# light_cube.net
KiCad netlist of a schematic drawn in EAGLE
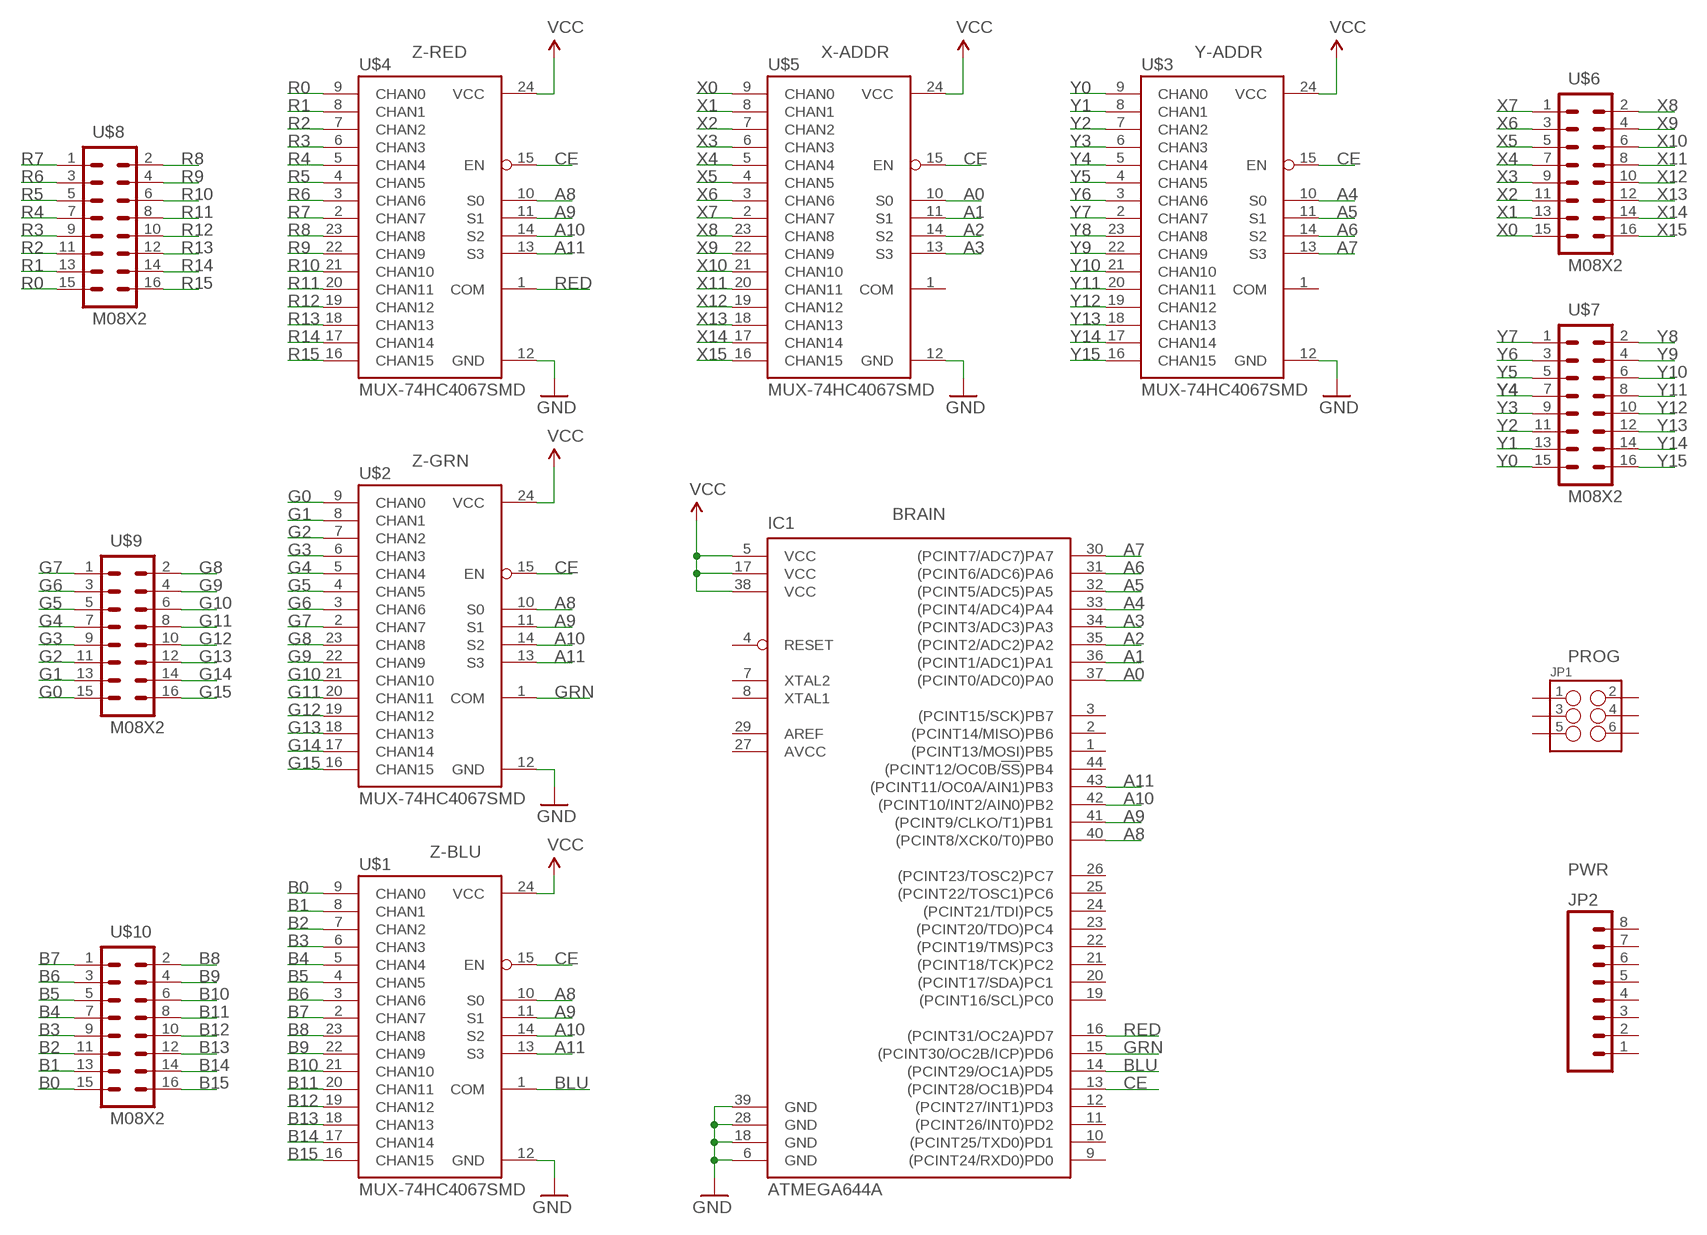
[diagram p0: schematic, sheet 1]

(export (version "E")
  (design (tool "Eeschema 10.0.6"))
  (components
    (comp (ref "IC1")
      (value "ATMEGA644A")
      (footprint "eagle-import:TQFP44")
      (fields (field (name "MPN") "ATMEGA644PV-10AU"))
      (libsource (lib "eagle-import") (part "ATMEGA644A"))
    )
    (comp (ref "JP1")
      (value "M03X2NO_SILK")
      (footprint "eagle-import:2X3-NS")
      (libsource (lib "eagle-import") (part "M03X2NO_SILK"))
    )
    (comp (ref "JP2")
      (value "M081X08")
      (footprint "eagle-import:1X08")
      (libsource (lib "eagle-import") (part "M081X08"))
    )
    (comp (ref "U$1")
      (value "MUX-74HC4067SMD")
      (footprint "eagle-import:SSOP24")
      (libsource (lib "eagle-import") (part "MUX-74HC4067SMD"))
    )
    (comp (ref "U$2")
      (value "MUX-74HC4067SMD")
      (footprint "eagle-import:SSOP24")
      (libsource (lib "eagle-import") (part "MUX-74HC4067SMD"))
    )
    (comp (ref "U$3")
      (value "MUX-74HC4067SMD")
      (footprint "eagle-import:SSOP24")
      (libsource (lib "eagle-import") (part "MUX-74HC4067SMD"))
    )
    (comp (ref "U$4")
      (value "MUX-74HC4067SMD")
      (footprint "eagle-import:SSOP24")
      (libsource (lib "eagle-import") (part "MUX-74HC4067SMD"))
    )
    (comp (ref "U$5")
      (value "MUX-74HC4067SMD")
      (footprint "eagle-import:SSOP24")
      (libsource (lib "eagle-import") (part "MUX-74HC4067SMD"))
    )
    (comp (ref "U$6")
      (value "M08X2")
      (footprint "eagle-import:2X8")
      (libsource (lib "eagle-import") (part "M08X2"))
    )
    (comp (ref "U$7")
      (value "M08X2")
      (footprint "eagle-import:2X8")
      (libsource (lib "eagle-import") (part "M08X2"))
    )
    (comp (ref "U$8")
      (value "M08X2")
      (footprint "eagle-import:2X8")
      (libsource (lib "eagle-import") (part "M08X2"))
    )
    (comp (ref "U$9")
      (value "M08X2")
      (footprint "eagle-import:2X8")
      (libsource (lib "eagle-import") (part "M08X2"))
    )
    (comp (ref "U$10")
      (value "M08X2")
      (footprint "eagle-import:2X8")
      (libsource (lib "eagle-import") (part "M08X2"))
    )
  )
  (nets
    (net (code "1") (name "/A0") (class "Default")
      (node (ref "IC1") (pin "37") (pinfunction "(PCINT0/ADC0)PA0_37") (pintype "bidirectional"))
      (node (ref "U$5") (pin "10") (pinfunction "S0_10") (pintype "input"))
    )
    (net (code "2") (name "/A1") (class "Default")
      (node (ref "IC1") (pin "36") (pinfunction "(PCINT1/ADC1)PA1_36") (pintype "bidirectional"))
      (node (ref "U$5") (pin "11") (pinfunction "S1_11") (pintype "input"))
    )
    (net (code "3") (name "/A2") (class "Default")
      (node (ref "IC1") (pin "35") (pinfunction "(PCINT2/ADC2)PA2_35") (pintype "bidirectional"))
      (node (ref "U$5") (pin "14") (pinfunction "S2_14") (pintype "input"))
    )
    (net (code "4") (name "/A3") (class "Default")
      (node (ref "IC1") (pin "34") (pinfunction "(PCINT3/ADC3)PA3_34") (pintype "bidirectional"))
      (node (ref "U$5") (pin "13") (pinfunction "S3_13") (pintype "input"))
    )
    (net (code "5") (name "/A4") (class "Default")
      (node (ref "IC1") (pin "33") (pinfunction "(PCINT4/ADC4)PA4_33") (pintype "bidirectional"))
      (node (ref "U$3") (pin "10") (pinfunction "S0_10") (pintype "input"))
    )
    (net (code "6") (name "/A5") (class "Default")
      (node (ref "IC1") (pin "32") (pinfunction "(PCINT5/ADC5)PA5_32") (pintype "bidirectional"))
      (node (ref "U$3") (pin "11") (pinfunction "S1_11") (pintype "input"))
    )
    (net (code "7") (name "/A6") (class "Default")
      (node (ref "IC1") (pin "31") (pinfunction "(PCINT6/ADC6)PA6_31") (pintype "bidirectional"))
      (node (ref "U$3") (pin "14") (pinfunction "S2_14") (pintype "input"))
    )
    (net (code "8") (name "/A7") (class "Default")
      (node (ref "IC1") (pin "30") (pinfunction "(PCINT7/ADC7)PA7_30") (pintype "bidirectional"))
      (node (ref "U$3") (pin "13") (pinfunction "S3_13") (pintype "input"))
    )
    (net (code "9") (name "/A8") (class "Default")
      (node (ref "IC1") (pin "40") (pinfunction "(PCINT8/XCK0/T0)PB0_40") (pintype "bidirectional"))
      (node (ref "U$1") (pin "10") (pinfunction "S0_10") (pintype "input"))
      (node (ref "U$2") (pin "10") (pinfunction "S0_10") (pintype "input"))
      (node (ref "U$4") (pin "10") (pinfunction "S0_10") (pintype "input"))
    )
    (net (code "10") (name "/A9") (class "Default")
      (node (ref "IC1") (pin "41") (pinfunction "(PCINT9/CLKO/T1)PB1_41") (pintype "bidirectional"))
      (node (ref "U$1") (pin "11") (pinfunction "S1_11") (pintype "input"))
      (node (ref "U$2") (pin "11") (pinfunction "S1_11") (pintype "input"))
      (node (ref "U$4") (pin "11") (pinfunction "S1_11") (pintype "input"))
    )
    (net (code "11") (name "/A10") (class "Default")
      (node (ref "IC1") (pin "42") (pinfunction "(PCINT10/INT2/AIN0)PB2_42") (pintype "bidirectional"))
      (node (ref "U$1") (pin "14") (pinfunction "S2_14") (pintype "input"))
      (node (ref "U$2") (pin "14") (pinfunction "S2_14") (pintype "input"))
      (node (ref "U$4") (pin "14") (pinfunction "S2_14") (pintype "input"))
    )
    (net (code "12") (name "/A11") (class "Default")
      (node (ref "IC1") (pin "43") (pinfunction "(PCINT11/OC0A/AIN1)PB3_43") (pintype "bidirectional"))
      (node (ref "U$1") (pin "13") (pinfunction "S3_13") (pintype "input"))
      (node (ref "U$2") (pin "13") (pinfunction "S3_13") (pintype "input"))
      (node (ref "U$4") (pin "13") (pinfunction "S3_13") (pintype "input"))
    )
    (net (code "13") (name "/AVCC") (class "Default")
      (node (ref "IC1") (pin "27") (pinfunction "AVCC_27") (pintype "power_in"))
    )
    (net (code "14") (name "/B0") (class "Default")
      (node (ref "U$1") (pin "9") (pinfunction "CHAN0_9") (pintype "bidirectional"))
      (node (ref "U$10") (pin "15") (pinfunction "15_15") (pintype "passive"))
    )
    (net (code "15") (name "/B1") (class "Default")
      (node (ref "U$1") (pin "8") (pinfunction "CHAN1_8") (pintype "bidirectional"))
      (node (ref "U$10") (pin "13") (pinfunction "13_13") (pintype "passive"))
    )
    (net (code "16") (name "/B2") (class "Default")
      (node (ref "U$1") (pin "7") (pinfunction "CHAN2_7") (pintype "bidirectional"))
      (node (ref "U$10") (pin "11") (pinfunction "11_11") (pintype "passive"))
    )
    (net (code "17") (name "/B3") (class "Default")
      (node (ref "U$1") (pin "6") (pinfunction "CHAN3_6") (pintype "bidirectional"))
      (node (ref "U$10") (pin "9") (pinfunction "9_9") (pintype "passive"))
    )
    (net (code "18") (name "/B4") (class "Default")
      (node (ref "U$1") (pin "5") (pinfunction "CHAN4_5") (pintype "bidirectional"))
      (node (ref "U$10") (pin "7") (pinfunction "7_7") (pintype "passive"))
    )
    (net (code "19") (name "/B5") (class "Default")
      (node (ref "U$1") (pin "4") (pinfunction "CHAN5_4") (pintype "bidirectional"))
      (node (ref "U$10") (pin "5") (pinfunction "5_5") (pintype "passive"))
    )
    (net (code "20") (name "/B6") (class "Default")
      (node (ref "U$1") (pin "3") (pinfunction "CHAN6_3") (pintype "bidirectional"))
      (node (ref "U$10") (pin "3") (pinfunction "3_3") (pintype "passive"))
    )
    (net (code "21") (name "/B7") (class "Default")
      (node (ref "U$1") (pin "2") (pinfunction "CHAN7_2") (pintype "bidirectional"))
      (node (ref "U$10") (pin "1") (pinfunction "1_1") (pintype "passive"))
    )
    (net (code "22") (name "/B8") (class "Default")
      (node (ref "U$1") (pin "23") (pinfunction "CHAN8_23") (pintype "bidirectional"))
      (node (ref "U$10") (pin "2") (pinfunction "2_2") (pintype "passive"))
    )
    (net (code "23") (name "/B9") (class "Default")
      (node (ref "U$1") (pin "22") (pinfunction "CHAN9_22") (pintype "bidirectional"))
      (node (ref "U$10") (pin "4") (pinfunction "4_4") (pintype "passive"))
    )
    (net (code "24") (name "/B10") (class "Default")
      (node (ref "U$1") (pin "21") (pinfunction "CHAN10_21") (pintype "bidirectional"))
      (node (ref "U$10") (pin "6") (pinfunction "6_6") (pintype "passive"))
    )
    (net (code "25") (name "/B11") (class "Default")
      (node (ref "U$1") (pin "20") (pinfunction "CHAN11_20") (pintype "bidirectional"))
      (node (ref "U$10") (pin "8") (pinfunction "8_8") (pintype "passive"))
    )
    (net (code "26") (name "/B12") (class "Default")
      (node (ref "U$1") (pin "19") (pinfunction "CHAN12_19") (pintype "bidirectional"))
      (node (ref "U$10") (pin "10") (pinfunction "10_10") (pintype "passive"))
    )
    (net (code "27") (name "/B13") (class "Default")
      (node (ref "U$1") (pin "18") (pinfunction "CHAN13_18") (pintype "bidirectional"))
      (node (ref "U$10") (pin "12") (pinfunction "12_12") (pintype "passive"))
    )
    (net (code "28") (name "/B14") (class "Default")
      (node (ref "U$1") (pin "17") (pinfunction "CHAN14_17") (pintype "bidirectional"))
      (node (ref "U$10") (pin "14") (pinfunction "14_14") (pintype "passive"))
    )
    (net (code "29") (name "/B15") (class "Default")
      (node (ref "U$1") (pin "16") (pinfunction "CHAN15_16") (pintype "bidirectional"))
      (node (ref "U$10") (pin "16") (pinfunction "16_16") (pintype "passive"))
    )
    (net (code "30") (name "/BLU") (class "Default")
      (node (ref "IC1") (pin "14") (pinfunction "(PCINT29/OC1A)PD5_14") (pintype "bidirectional"))
      (node (ref "U$1") (pin "1") (pinfunction "COM_1") (pintype "bidirectional"))
    )
    (net (code "31") (name "/CE") (class "Default")
      (node (ref "IC1") (pin "13") (pinfunction "(PCINT28/OC1B)PD4_13") (pintype "bidirectional"))
      (node (ref "U$1") (pin "15") (pinfunction "EN_15") (pintype "input"))
      (node (ref "U$2") (pin "15") (pinfunction "EN_15") (pintype "input"))
      (node (ref "U$3") (pin "15") (pinfunction "EN_15") (pintype "input"))
      (node (ref "U$4") (pin "15") (pinfunction "EN_15") (pintype "input"))
      (node (ref "U$5") (pin "15") (pinfunction "EN_15") (pintype "input"))
    )
    (net (code "32") (name "/G0") (class "Default")
      (node (ref "U$2") (pin "9") (pinfunction "CHAN0_9") (pintype "bidirectional"))
      (node (ref "U$9") (pin "15") (pinfunction "15_15") (pintype "passive"))
    )
    (net (code "33") (name "/G1") (class "Default")
      (node (ref "U$2") (pin "8") (pinfunction "CHAN1_8") (pintype "bidirectional"))
      (node (ref "U$9") (pin "13") (pinfunction "13_13") (pintype "passive"))
    )
    (net (code "34") (name "/G2") (class "Default")
      (node (ref "U$2") (pin "7") (pinfunction "CHAN2_7") (pintype "bidirectional"))
      (node (ref "U$9") (pin "11") (pinfunction "11_11") (pintype "passive"))
    )
    (net (code "35") (name "/G3") (class "Default")
      (node (ref "U$2") (pin "6") (pinfunction "CHAN3_6") (pintype "bidirectional"))
      (node (ref "U$9") (pin "9") (pinfunction "9_9") (pintype "passive"))
    )
    (net (code "36") (name "/G4") (class "Default")
      (node (ref "U$2") (pin "5") (pinfunction "CHAN4_5") (pintype "bidirectional"))
      (node (ref "U$9") (pin "7") (pinfunction "7_7") (pintype "passive"))
    )
    (net (code "37") (name "/G5") (class "Default")
      (node (ref "U$2") (pin "4") (pinfunction "CHAN5_4") (pintype "bidirectional"))
      (node (ref "U$9") (pin "5") (pinfunction "5_5") (pintype "passive"))
    )
    (net (code "38") (name "/G6") (class "Default")
      (node (ref "U$2") (pin "3") (pinfunction "CHAN6_3") (pintype "bidirectional"))
      (node (ref "U$9") (pin "3") (pinfunction "3_3") (pintype "passive"))
    )
    (net (code "39") (name "/G7") (class "Default")
      (node (ref "U$2") (pin "2") (pinfunction "CHAN7_2") (pintype "bidirectional"))
      (node (ref "U$9") (pin "1") (pinfunction "1_1") (pintype "passive"))
    )
    (net (code "40") (name "/G8") (class "Default")
      (node (ref "U$2") (pin "23") (pinfunction "CHAN8_23") (pintype "bidirectional"))
      (node (ref "U$9") (pin "2") (pinfunction "2_2") (pintype "passive"))
    )
    (net (code "41") (name "/G9") (class "Default")
      (node (ref "U$2") (pin "22") (pinfunction "CHAN9_22") (pintype "bidirectional"))
      (node (ref "U$9") (pin "4") (pinfunction "4_4") (pintype "passive"))
    )
    (net (code "42") (name "/G10") (class "Default")
      (node (ref "U$2") (pin "21") (pinfunction "CHAN10_21") (pintype "bidirectional"))
      (node (ref "U$9") (pin "6") (pinfunction "6_6") (pintype "passive"))
    )
    (net (code "43") (name "/G11") (class "Default")
      (node (ref "U$2") (pin "20") (pinfunction "CHAN11_20") (pintype "bidirectional"))
      (node (ref "U$9") (pin "8") (pinfunction "8_8") (pintype "passive"))
    )
    (net (code "44") (name "/G12") (class "Default")
      (node (ref "U$2") (pin "19") (pinfunction "CHAN12_19") (pintype "bidirectional"))
      (node (ref "U$9") (pin "10") (pinfunction "10_10") (pintype "passive"))
    )
    (net (code "45") (name "/G13") (class "Default")
      (node (ref "U$2") (pin "18") (pinfunction "CHAN13_18") (pintype "bidirectional"))
      (node (ref "U$9") (pin "12") (pinfunction "12_12") (pintype "passive"))
    )
    (net (code "46") (name "/G14") (class "Default")
      (node (ref "U$2") (pin "17") (pinfunction "CHAN14_17") (pintype "bidirectional"))
      (node (ref "U$9") (pin "14") (pinfunction "14_14") (pintype "passive"))
    )
    (net (code "47") (name "/G15") (class "Default")
      (node (ref "U$2") (pin "16") (pinfunction "CHAN15_16") (pintype "bidirectional"))
      (node (ref "U$9") (pin "16") (pinfunction "16_16") (pintype "passive"))
    )
    (net (code "48") (name "/GRN") (class "Default")
      (node (ref "IC1") (pin "15") (pinfunction "(PCINT30/OC2B/ICP)PD6_15") (pintype "bidirectional"))
      (node (ref "U$2") (pin "1") (pinfunction "COM_1") (pintype "bidirectional"))
    )
    (net (code "49") (name "/R0") (class "Default")
      (node (ref "U$4") (pin "9") (pinfunction "CHAN0_9") (pintype "bidirectional"))
      (node (ref "U$8") (pin "15") (pinfunction "15_15") (pintype "passive"))
    )
    (net (code "50") (name "/R1") (class "Default")
      (node (ref "U$4") (pin "8") (pinfunction "CHAN1_8") (pintype "bidirectional"))
      (node (ref "U$8") (pin "13") (pinfunction "13_13") (pintype "passive"))
    )
    (net (code "51") (name "/R2") (class "Default")
      (node (ref "U$4") (pin "7") (pinfunction "CHAN2_7") (pintype "bidirectional"))
      (node (ref "U$8") (pin "11") (pinfunction "11_11") (pintype "passive"))
    )
    (net (code "52") (name "/R3") (class "Default")
      (node (ref "U$4") (pin "6") (pinfunction "CHAN3_6") (pintype "bidirectional"))
      (node (ref "U$8") (pin "9") (pinfunction "9_9") (pintype "passive"))
    )
    (net (code "53") (name "/R4") (class "Default")
      (node (ref "U$4") (pin "5") (pinfunction "CHAN4_5") (pintype "bidirectional"))
      (node (ref "U$8") (pin "7") (pinfunction "7_7") (pintype "passive"))
    )
    (net (code "54") (name "/R5") (class "Default")
      (node (ref "U$4") (pin "4") (pinfunction "CHAN5_4") (pintype "bidirectional"))
      (node (ref "U$8") (pin "5") (pinfunction "5_5") (pintype "passive"))
    )
    (net (code "55") (name "/R6") (class "Default")
      (node (ref "U$4") (pin "3") (pinfunction "CHAN6_3") (pintype "bidirectional"))
      (node (ref "U$8") (pin "3") (pinfunction "3_3") (pintype "passive"))
    )
    (net (code "56") (name "/R7") (class "Default")
      (node (ref "U$4") (pin "2") (pinfunction "CHAN7_2") (pintype "bidirectional"))
      (node (ref "U$8") (pin "1") (pinfunction "1_1") (pintype "passive"))
    )
    (net (code "57") (name "/R8") (class "Default")
      (node (ref "U$4") (pin "23") (pinfunction "CHAN8_23") (pintype "bidirectional"))
      (node (ref "U$8") (pin "2") (pinfunction "2_2") (pintype "passive"))
    )
    (net (code "58") (name "/R9") (class "Default")
      (node (ref "U$4") (pin "22") (pinfunction "CHAN9_22") (pintype "bidirectional"))
      (node (ref "U$8") (pin "4") (pinfunction "4_4") (pintype "passive"))
    )
    (net (code "59") (name "/R10") (class "Default")
      (node (ref "U$4") (pin "21") (pinfunction "CHAN10_21") (pintype "bidirectional"))
      (node (ref "U$8") (pin "6") (pinfunction "6_6") (pintype "passive"))
    )
    (net (code "60") (name "/R11") (class "Default")
      (node (ref "U$4") (pin "20") (pinfunction "CHAN11_20") (pintype "bidirectional"))
      (node (ref "U$8") (pin "8") (pinfunction "8_8") (pintype "passive"))
    )
    (net (code "61") (name "/R12") (class "Default")
      (node (ref "U$4") (pin "19") (pinfunction "CHAN12_19") (pintype "bidirectional"))
      (node (ref "U$8") (pin "10") (pinfunction "10_10") (pintype "passive"))
    )
    (net (code "62") (name "/R13") (class "Default")
      (node (ref "U$4") (pin "18") (pinfunction "CHAN13_18") (pintype "bidirectional"))
      (node (ref "U$8") (pin "12") (pinfunction "12_12") (pintype "passive"))
    )
    (net (code "63") (name "/R14") (class "Default")
      (node (ref "U$4") (pin "17") (pinfunction "CHAN14_17") (pintype "bidirectional"))
      (node (ref "U$8") (pin "14") (pinfunction "14_14") (pintype "passive"))
    )
    (net (code "64") (name "/R15") (class "Default")
      (node (ref "U$4") (pin "16") (pinfunction "CHAN15_16") (pintype "bidirectional"))
      (node (ref "U$8") (pin "16") (pinfunction "16_16") (pintype "passive"))
    )
    (net (code "65") (name "/RED") (class "Default")
      (node (ref "IC1") (pin "16") (pinfunction "(PCINT31/OC2A)PD7_16") (pintype "bidirectional"))
      (node (ref "U$4") (pin "1") (pinfunction "COM_1") (pintype "bidirectional"))
    )
    (net (code "66") (name "/X0") (class "Default")
      (node (ref "U$5") (pin "9") (pinfunction "CHAN0_9") (pintype "bidirectional"))
      (node (ref "U$6") (pin "15") (pinfunction "15_15") (pintype "passive"))
    )
    (net (code "67") (name "/X1") (class "Default")
      (node (ref "U$5") (pin "8") (pinfunction "CHAN1_8") (pintype "bidirectional"))
      (node (ref "U$6") (pin "13") (pinfunction "13_13") (pintype "passive"))
    )
    (net (code "68") (name "/X2") (class "Default")
      (node (ref "U$5") (pin "7") (pinfunction "CHAN2_7") (pintype "bidirectional"))
      (node (ref "U$6") (pin "11") (pinfunction "11_11") (pintype "passive"))
    )
    (net (code "69") (name "/X3") (class "Default")
      (node (ref "U$5") (pin "6") (pinfunction "CHAN3_6") (pintype "bidirectional"))
      (node (ref "U$6") (pin "9") (pinfunction "9_9") (pintype "passive"))
    )
    (net (code "70") (name "/X4") (class "Default")
      (node (ref "U$5") (pin "5") (pinfunction "CHAN4_5") (pintype "bidirectional"))
      (node (ref "U$6") (pin "7") (pinfunction "7_7") (pintype "passive"))
    )
    (net (code "71") (name "/X5") (class "Default")
      (node (ref "U$5") (pin "4") (pinfunction "CHAN5_4") (pintype "bidirectional"))
      (node (ref "U$6") (pin "5") (pinfunction "5_5") (pintype "passive"))
    )
    (net (code "72") (name "/X6") (class "Default")
      (node (ref "U$5") (pin "3") (pinfunction "CHAN6_3") (pintype "bidirectional"))
      (node (ref "U$6") (pin "3") (pinfunction "3_3") (pintype "passive"))
    )
    (net (code "73") (name "/X7") (class "Default")
      (node (ref "U$5") (pin "2") (pinfunction "CHAN7_2") (pintype "bidirectional"))
      (node (ref "U$6") (pin "1") (pinfunction "1_1") (pintype "passive"))
    )
    (net (code "74") (name "/X8") (class "Default")
      (node (ref "U$5") (pin "23") (pinfunction "CHAN8_23") (pintype "bidirectional"))
      (node (ref "U$6") (pin "2") (pinfunction "2_2") (pintype "passive"))
    )
    (net (code "75") (name "/X9") (class "Default")
      (node (ref "U$5") (pin "22") (pinfunction "CHAN9_22") (pintype "bidirectional"))
      (node (ref "U$6") (pin "4") (pinfunction "4_4") (pintype "passive"))
    )
    (net (code "76") (name "/X10") (class "Default")
      (node (ref "U$5") (pin "21") (pinfunction "CHAN10_21") (pintype "bidirectional"))
      (node (ref "U$6") (pin "6") (pinfunction "6_6") (pintype "passive"))
    )
    (net (code "77") (name "/X11") (class "Default")
      (node (ref "U$5") (pin "20") (pinfunction "CHAN11_20") (pintype "bidirectional"))
      (node (ref "U$6") (pin "8") (pinfunction "8_8") (pintype "passive"))
    )
    (net (code "78") (name "/X12") (class "Default")
      (node (ref "U$5") (pin "19") (pinfunction "CHAN12_19") (pintype "bidirectional"))
      (node (ref "U$6") (pin "10") (pinfunction "10_10") (pintype "passive"))
    )
    (net (code "79") (name "/X13") (class "Default")
      (node (ref "U$5") (pin "18") (pinfunction "CHAN13_18") (pintype "bidirectional"))
      (node (ref "U$6") (pin "12") (pinfunction "12_12") (pintype "passive"))
    )
    (net (code "80") (name "/X14") (class "Default")
      (node (ref "U$5") (pin "17") (pinfunction "CHAN14_17") (pintype "bidirectional"))
      (node (ref "U$6") (pin "14") (pinfunction "14_14") (pintype "passive"))
    )
    (net (code "81") (name "/X15") (class "Default")
      (node (ref "U$5") (pin "16") (pinfunction "CHAN15_16") (pintype "bidirectional"))
      (node (ref "U$6") (pin "16") (pinfunction "16_16") (pintype "passive"))
    )
    (net (code "82") (name "/Y0") (class "Default")
      (node (ref "U$3") (pin "9") (pinfunction "CHAN0_9") (pintype "bidirectional"))
      (node (ref "U$7") (pin "15") (pinfunction "15_15") (pintype "passive"))
    )
    (net (code "83") (name "/Y1") (class "Default")
      (node (ref "U$3") (pin "8") (pinfunction "CHAN1_8") (pintype "bidirectional"))
      (node (ref "U$7") (pin "13") (pinfunction "13_13") (pintype "passive"))
    )
    (net (code "84") (name "/Y2") (class "Default")
      (node (ref "U$3") (pin "7") (pinfunction "CHAN2_7") (pintype "bidirectional"))
      (node (ref "U$7") (pin "11") (pinfunction "11_11") (pintype "passive"))
    )
    (net (code "85") (name "/Y3") (class "Default")
      (node (ref "U$3") (pin "6") (pinfunction "CHAN3_6") (pintype "bidirectional"))
      (node (ref "U$7") (pin "9") (pinfunction "9_9") (pintype "passive"))
    )
    (net (code "86") (name "/Y4") (class "Default")
      (node (ref "U$3") (pin "5") (pinfunction "CHAN4_5") (pintype "bidirectional"))
      (node (ref "U$7") (pin "7") (pinfunction "7_7") (pintype "passive"))
    )
    (net (code "87") (name "/Y5") (class "Default")
      (node (ref "U$3") (pin "4") (pinfunction "CHAN5_4") (pintype "bidirectional"))
      (node (ref "U$7") (pin "5") (pinfunction "5_5") (pintype "passive"))
    )
    (net (code "88") (name "/Y6") (class "Default")
      (node (ref "U$3") (pin "3") (pinfunction "CHAN6_3") (pintype "bidirectional"))
      (node (ref "U$7") (pin "3") (pinfunction "3_3") (pintype "passive"))
    )
    (net (code "89") (name "/Y7") (class "Default")
      (node (ref "U$3") (pin "2") (pinfunction "CHAN7_2") (pintype "bidirectional"))
      (node (ref "U$7") (pin "1") (pinfunction "1_1") (pintype "passive"))
    )
    (net (code "90") (name "/Y8") (class "Default")
      (node (ref "U$3") (pin "23") (pinfunction "CHAN8_23") (pintype "bidirectional"))
      (node (ref "U$7") (pin "2") (pinfunction "2_2") (pintype "passive"))
    )
    (net (code "91") (name "/Y9") (class "Default")
      (node (ref "U$3") (pin "22") (pinfunction "CHAN9_22") (pintype "bidirectional"))
      (node (ref "U$7") (pin "4") (pinfunction "4_4") (pintype "passive"))
    )
    (net (code "92") (name "/Y10") (class "Default")
      (node (ref "U$3") (pin "21") (pinfunction "CHAN10_21") (pintype "bidirectional"))
      (node (ref "U$7") (pin "6") (pinfunction "6_6") (pintype "passive"))
    )
    (net (code "93") (name "/Y11") (class "Default")
      (node (ref "U$3") (pin "20") (pinfunction "CHAN11_20") (pintype "bidirectional"))
      (node (ref "U$7") (pin "8") (pinfunction "8_8") (pintype "passive"))
    )
    (net (code "94") (name "/Y12") (class "Default")
      (node (ref "U$3") (pin "19") (pinfunction "CHAN12_19") (pintype "bidirectional"))
      (node (ref "U$7") (pin "10") (pinfunction "10_10") (pintype "passive"))
    )
    (net (code "95") (name "/Y13") (class "Default")
      (node (ref "U$3") (pin "18") (pinfunction "CHAN13_18") (pintype "bidirectional"))
      (node (ref "U$7") (pin "12") (pinfunction "12_12") (pintype "passive"))
    )
    (net (code "96") (name "/Y14") (class "Default")
      (node (ref "U$3") (pin "17") (pinfunction "CHAN14_17") (pintype "bidirectional"))
      (node (ref "U$7") (pin "14") (pinfunction "14_14") (pintype "passive"))
    )
    (net (code "97") (name "/Y15") (class "Default")
      (node (ref "U$3") (pin "16") (pinfunction "CHAN15_16") (pintype "bidirectional"))
      (node (ref "U$7") (pin "16") (pinfunction "16_16") (pintype "passive"))
    )
    (net (code "98") (name "GND") (class "Default")
      (node (ref "IC1") (pin "18") (pinfunction "GND_18") (pintype "power_in"))
      (node (ref "IC1") (pin "28") (pinfunction "GND_28") (pintype "power_in"))
      (node (ref "IC1") (pin "39") (pinfunction "GND_39") (pintype "power_in"))
      (node (ref "IC1") (pin "6") (pinfunction "GND_6") (pintype "power_in"))
      (node (ref "U$1") (pin "12") (pinfunction "GND_12") (pintype "bidirectional"))
      (node (ref "U$2") (pin "12") (pinfunction "GND_12") (pintype "bidirectional"))
      (node (ref "U$3") (pin "12") (pinfunction "GND_12") (pintype "bidirectional"))
      (node (ref "U$4") (pin "12") (pinfunction "GND_12") (pintype "bidirectional"))
      (node (ref "U$5") (pin "12") (pinfunction "GND_12") (pintype "bidirectional"))
    )
    (net (code "99") (name "VCC") (class "Default")
      (node (ref "IC1") (pin "17") (pinfunction "VCC_17") (pintype "power_in"))
      (node (ref "IC1") (pin "38") (pinfunction "VCC_38") (pintype "power_in"))
      (node (ref "IC1") (pin "5") (pinfunction "VCC_5") (pintype "power_in"))
      (node (ref "U$1") (pin "24") (pinfunction "VCC_24") (pintype "bidirectional"))
      (node (ref "U$2") (pin "24") (pinfunction "VCC_24") (pintype "bidirectional"))
      (node (ref "U$3") (pin "24") (pinfunction "VCC_24") (pintype "bidirectional"))
      (node (ref "U$4") (pin "24") (pinfunction "VCC_24") (pintype "bidirectional"))
      (node (ref "U$5") (pin "24") (pinfunction "VCC_24") (pintype "bidirectional"))
    )
    (net (code "100") (name "unconnected-(IC1-(PCINT12{slash}OC0B{slash}~{SS})PB4-Pad44)") (class "Default")
      (node (ref "IC1") (pin "44") (pinfunction "(PCINT12/OC0B/~{SS})PB4_44") (pintype "bidirectional"))
    )
    (net (code "101") (name "unconnected-(IC1-(PCINT13{slash}MOSI)PB5-Pad1)") (class "Default")
      (node (ref "IC1") (pin "1") (pinfunction "(PCINT13/MOSI)PB5_1") (pintype "bidirectional"))
    )
    (net (code "102") (name "unconnected-(IC1-(PCINT14{slash}MISO)PB6-Pad2)") (class "Default")
      (node (ref "IC1") (pin "2") (pinfunction "(PCINT14/MISO)PB6_2") (pintype "bidirectional"))
    )
    (net (code "103") (name "unconnected-(IC1-(PCINT15{slash}SCK)PB7-Pad3)") (class "Default")
      (node (ref "IC1") (pin "3") (pinfunction "(PCINT15/SCK)PB7_3") (pintype "bidirectional"))
    )
    (net (code "104") (name "unconnected-(IC1-(PCINT16{slash}SCL)PC0-Pad19)") (class "Default")
      (node (ref "IC1") (pin "19") (pinfunction "(PCINT16/SCL)PC0_19") (pintype "output"))
    )
    (net (code "105") (name "unconnected-(IC1-(PCINT17{slash}SDA)PC1-Pad20)") (class "Default")
      (node (ref "IC1") (pin "20") (pinfunction "(PCINT17/SDA)PC1_20") (pintype "output"))
    )
    (net (code "106") (name "unconnected-(IC1-(PCINT18{slash}TCK)PC2-Pad21)") (class "Default")
      (node (ref "IC1") (pin "21") (pinfunction "(PCINT18/TCK)PC2_21") (pintype "output"))
    )
    (net (code "107") (name "unconnected-(IC1-(PCINT19{slash}TMS)PC3-Pad22)") (class "Default")
      (node (ref "IC1") (pin "22") (pinfunction "(PCINT19/TMS)PC3_22") (pintype "output"))
    )
    (net (code "108") (name "unconnected-(IC1-(PCINT20{slash}TDO)PC4-Pad23)") (class "Default")
      (node (ref "IC1") (pin "23") (pinfunction "(PCINT20/TDO)PC4_23") (pintype "output"))
    )
    (net (code "109") (name "unconnected-(IC1-(PCINT21{slash}TDI)PC5-Pad24)") (class "Default")
      (node (ref "IC1") (pin "24") (pinfunction "(PCINT21/TDI)PC5_24") (pintype "output"))
    )
    (net (code "110") (name "unconnected-(IC1-(PCINT22{slash}TOSC1)PC6-Pad25)") (class "Default")
      (node (ref "IC1") (pin "25") (pinfunction "(PCINT22/TOSC1)PC6_25") (pintype "output"))
    )
    (net (code "111") (name "unconnected-(IC1-(PCINT23{slash}TOSC2)PC7-Pad26)") (class "Default")
      (node (ref "IC1") (pin "26") (pinfunction "(PCINT23/TOSC2)PC7_26") (pintype "output"))
    )
    (net (code "112") (name "unconnected-(IC1-(PCINT24{slash}RXD0)PD0-Pad9)") (class "Default")
      (node (ref "IC1") (pin "9") (pinfunction "(PCINT24/RXD0)PD0_9") (pintype "bidirectional"))
    )
    (net (code "113") (name "unconnected-(IC1-(PCINT25{slash}TXD0)PD1-Pad10)") (class "Default")
      (node (ref "IC1") (pin "10") (pinfunction "(PCINT25/TXD0)PD1_10") (pintype "bidirectional"))
    )
    (net (code "114") (name "unconnected-(IC1-(PCINT26{slash}INT0)PD2-Pad11)") (class "Default")
      (node (ref "IC1") (pin "11") (pinfunction "(PCINT26/INT0)PD2_11") (pintype "bidirectional"))
    )
    (net (code "115") (name "unconnected-(IC1-(PCINT27{slash}INT1)PD3-Pad12)") (class "Default")
      (node (ref "IC1") (pin "12") (pinfunction "(PCINT27/INT1)PD3_12") (pintype "bidirectional"))
    )
    (net (code "116") (name "unconnected-(IC1-AREF-Pad29)") (class "Default")
      (node (ref "IC1") (pin "29") (pinfunction "AREF_29") (pintype "passive"))
    )
    (net (code "117") (name "unconnected-(IC1-RESET-Pad4)") (class "Default")
      (node (ref "IC1") (pin "4") (pinfunction "RESET_4") (pintype "input"))
    )
    (net (code "118") (name "unconnected-(IC1-XTAL1-Pad8)") (class "Default")
      (node (ref "IC1") (pin "8") (pinfunction "XTAL1_8") (pintype "bidirectional"))
    )
    (net (code "119") (name "unconnected-(IC1-XTAL2-Pad7)") (class "Default")
      (node (ref "IC1") (pin "7") (pinfunction "XTAL2_7") (pintype "bidirectional"))
    )
    (net (code "120") (name "unconnected-(JP1-Pad1)") (class "Default")
      (node (ref "JP1") (pin "1") (pinfunction "1_1") (pintype "bidirectional"))
    )
    (net (code "121") (name "unconnected-(JP1-Pad2)") (class "Default")
      (node (ref "JP1") (pin "2") (pinfunction "2_2") (pintype "bidirectional"))
    )
    (net (code "122") (name "unconnected-(JP1-Pad3)") (class "Default")
      (node (ref "JP1") (pin "3") (pinfunction "3_3") (pintype "bidirectional"))
    )
    (net (code "123") (name "unconnected-(JP1-Pad4)") (class "Default")
      (node (ref "JP1") (pin "4") (pinfunction "4_4") (pintype "bidirectional"))
    )
    (net (code "124") (name "unconnected-(JP1-Pad5)") (class "Default")
      (node (ref "JP1") (pin "5") (pinfunction "5_5") (pintype "bidirectional"))
    )
    (net (code "125") (name "unconnected-(JP1-Pad6)") (class "Default")
      (node (ref "JP1") (pin "6") (pinfunction "6_6") (pintype "bidirectional"))
    )
    (net (code "126") (name "unconnected-(JP2-Pad1)") (class "Default")
      (node (ref "JP2") (pin "1") (pinfunction "1_1") (pintype "passive"))
    )
    (net (code "127") (name "unconnected-(JP2-Pad2)") (class "Default")
      (node (ref "JP2") (pin "2") (pinfunction "2_2") (pintype "passive"))
    )
    (net (code "128") (name "unconnected-(JP2-Pad3)") (class "Default")
      (node (ref "JP2") (pin "3") (pinfunction "3_3") (pintype "passive"))
    )
    (net (code "129") (name "unconnected-(JP2-Pad4)") (class "Default")
      (node (ref "JP2") (pin "4") (pinfunction "4_4") (pintype "passive"))
    )
    (net (code "130") (name "unconnected-(JP2-Pad5)") (class "Default")
      (node (ref "JP2") (pin "5") (pinfunction "5_5") (pintype "passive"))
    )
    (net (code "131") (name "unconnected-(JP2-Pad6)") (class "Default")
      (node (ref "JP2") (pin "6") (pinfunction "6_6") (pintype "passive"))
    )
    (net (code "132") (name "unconnected-(JP2-Pad7)") (class "Default")
      (node (ref "JP2") (pin "7") (pinfunction "7_7") (pintype "passive"))
    )
    (net (code "133") (name "unconnected-(JP2-Pad8)") (class "Default")
      (node (ref "JP2") (pin "8") (pinfunction "8_8") (pintype "passive"))
    )
    (net (code "134") (name "unconnected-(U$3-COM-Pad1)") (class "Default")
      (node (ref "U$3") (pin "1") (pinfunction "COM_1") (pintype "bidirectional"))
    )
    (net (code "135") (name "unconnected-(U$5-COM-Pad1)") (class "Default")
      (node (ref "U$5") (pin "1") (pinfunction "COM_1") (pintype "bidirectional"))
    )
  )
)
